# Esquema_V2.net
KiCad netlist of a schematic drawn in Altium Designer
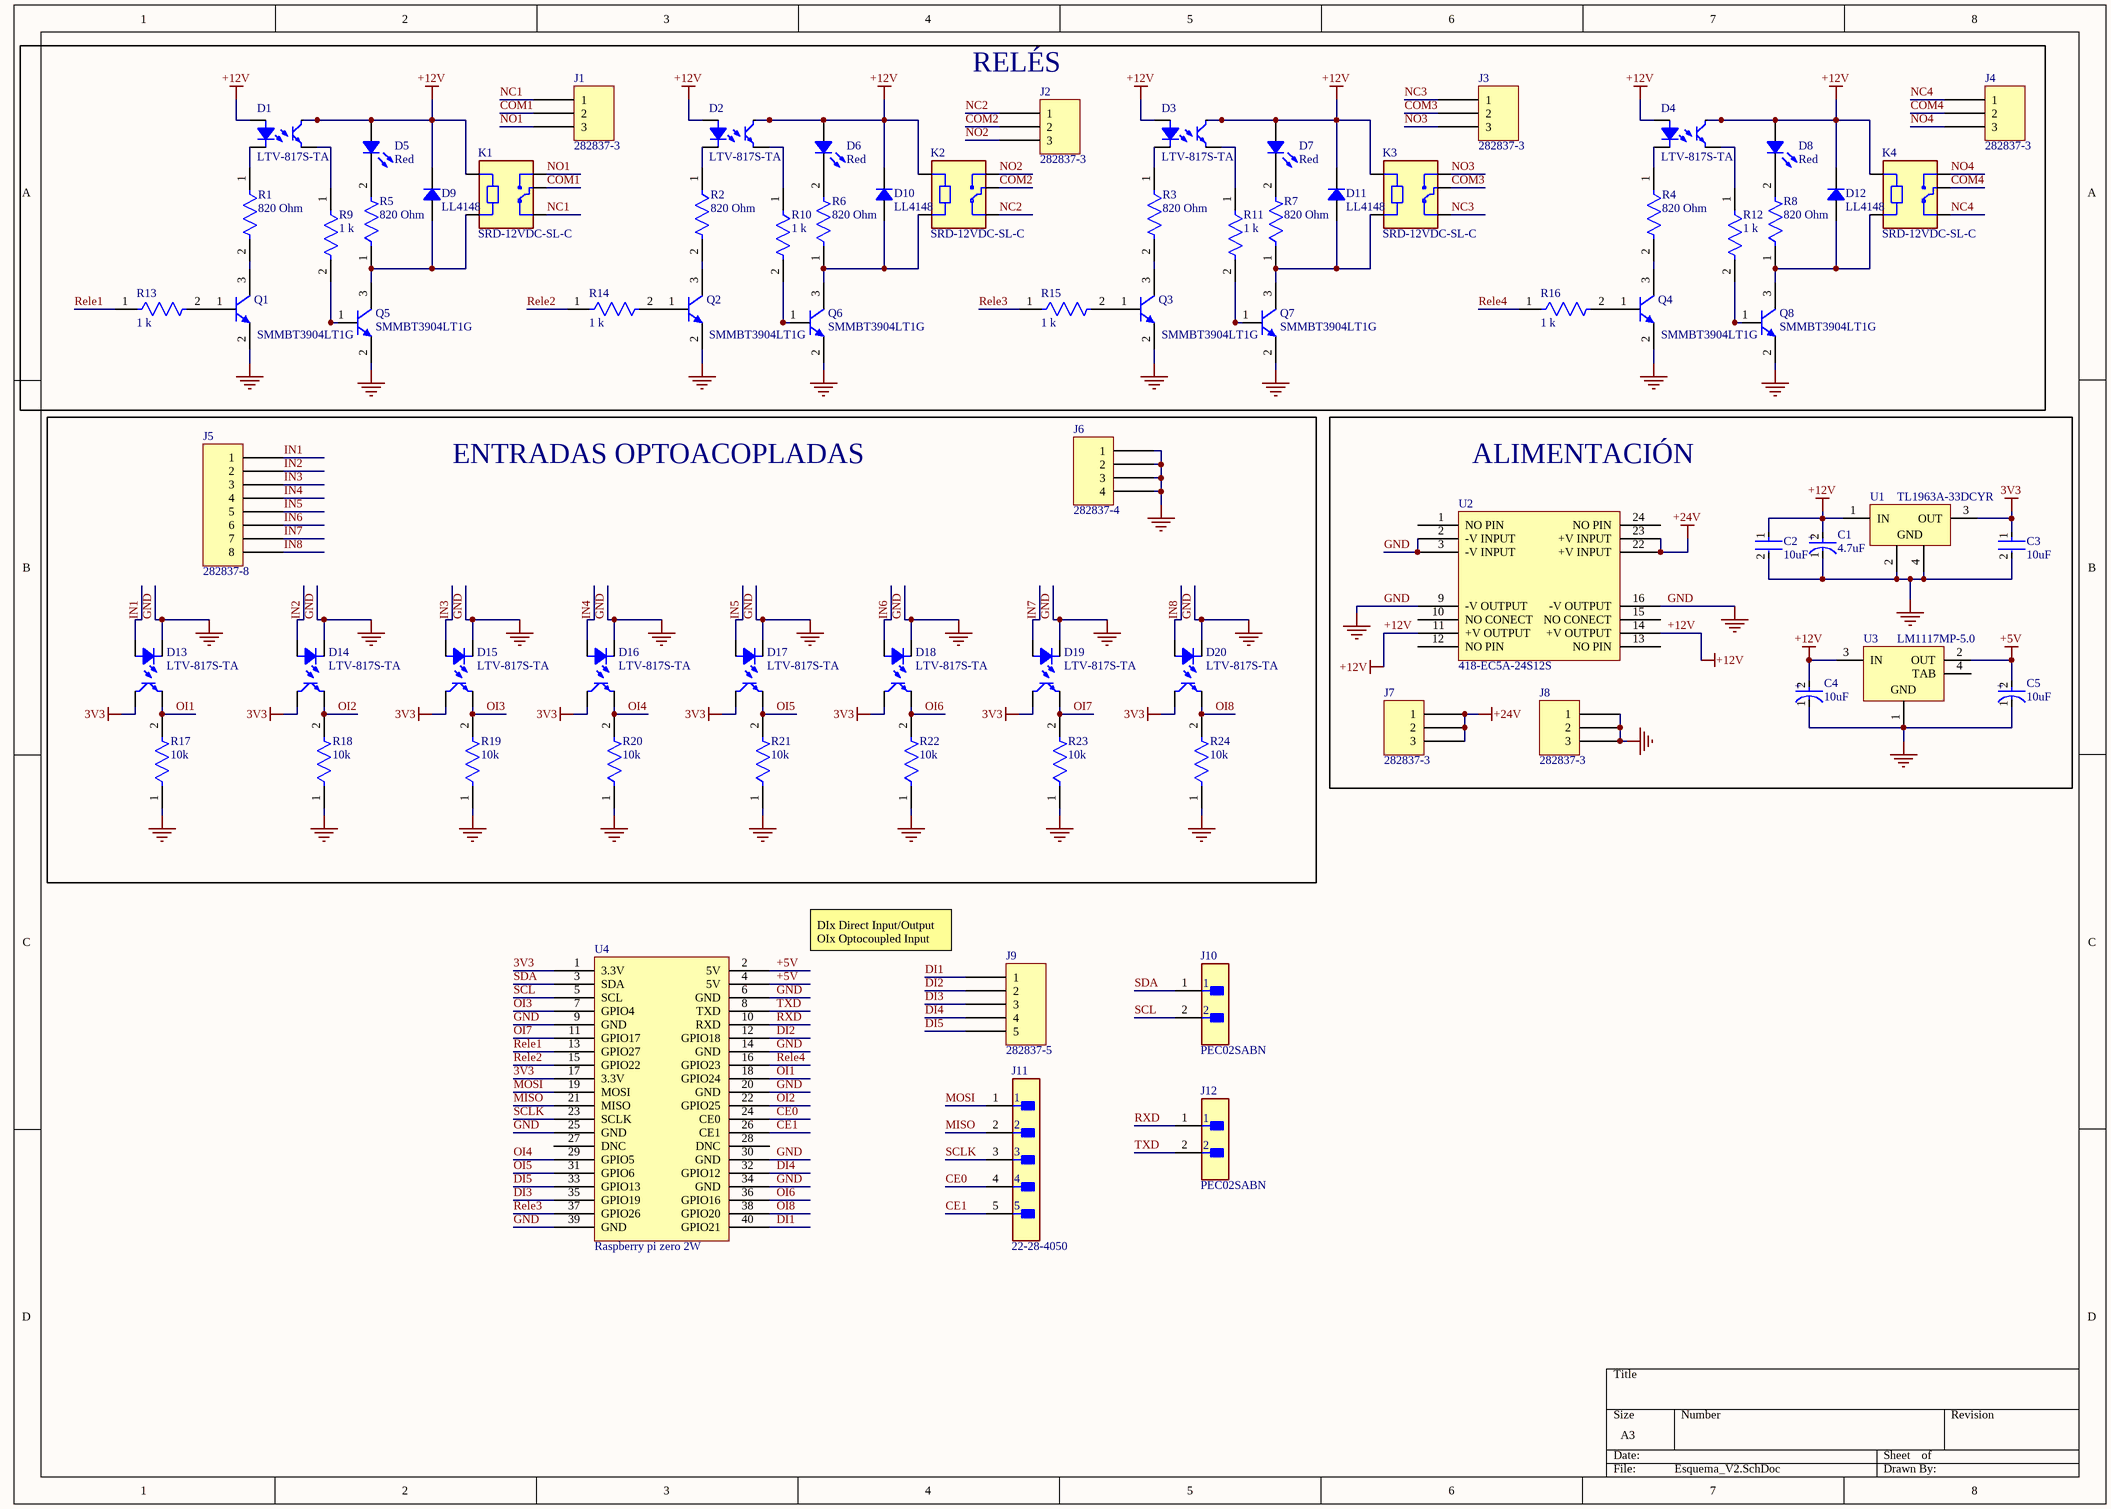
[diagram p0: Esquema_V2.SchDoc]

(export (version "E")
  (design (tool "Eeschema 10.0.6"))
  (components
    (comp (ref "C1")
      (value "4.7uF")
      (footprint "FP-T491A475M016AT-MFG")
      (description "T491A475M016AT CAP TANT 4.7UF 20% 16V 1206")
      (fields (field (name "TOLERANCE") "20%"))
      (libsource (lib "Altium Content Vault") (part "a00bbbee19879c290e62620ae7e47b1"))
    )
    (comp (ref "C2")
      (value "10uF")
      (footprint "FP-C2012-125-0_2-IPC_B")
      (description "C2012X5R1E106K125AB Multilayer Ceramic Capacitors 10μF ±10% 25V X5R SMD 0805")
      (fields (field (name "VOLTAGE") "25V") (field (name "TOLERANCE") "10%"))
      (libsource (lib "Altium Content Vault") (part "b4654b650e69147ec39a6b967a45e02"))
    )
    (comp (ref "C3")
      (value "10uF")
      (footprint "FP-C2012-125-0_2-IPC_B")
      (description "C2012X5R1E106K125AB Multilayer Ceramic Capacitors 10μF ±10% 25V X5R SMD 0805")
      (fields (field (name "VOLTAGE") "25V") (field (name "TOLERANCE") "10%"))
      (libsource (lib "Altium Content Vault") (part "b4654b650e69147ec39a6b967a45e02"))
    )
    (comp (ref "C4")
      (value "10uF")
      (footprint "FP-TAJA-MFG")
      (description "TAJA106M010RNJ 10uF 10V  ±20% 3Ω 1206  SMD Tantalum Capacitor")
      (fields (field (name "TOLERANCE") "20%") (field (name "VOLTAGE") "10V"))
      (libsource (lib "Altium Content Vault") (part "203bc49f2ac43e59fd269a8c329ed05"))
    )
    (comp (ref "C5")
      (value "10uF")
      (footprint "FP-TAJA-MFG")
      (description "TAJA106M010RNJ 10uF 10V  ±20% 3Ω 1206  SMD Tantalum Capacitor")
      (fields (field (name "TOLERANCE") "20%") (field (name "VOLTAGE") "10V"))
      (libsource (lib "Altium Content Vault") (part "203bc49f2ac43e59fd269a8c329ed05"))
    )
    (comp (ref "D1")
      (value "LTV-817S-TA")
      (footprint "LITEON LTV-817")
      (description "OPTOISOLATR 5KV TRANSISTOR 4-SMD")
      (fields (field (name "MANUFACTURER") "Lite-On Inc."))
      (libsource (lib "Celestial Altium Library - altium_library") (part "Optoisolator"))
    )
    (comp (ref "D2")
      (value "LTV-817S-TA")
      (footprint "LITEON LTV-817")
      (description "OPTOISOLATR 5KV TRANSISTOR 4-SMD")
      (fields (field (name "MANUFACTURER") "Lite-On Inc."))
      (libsource (lib "Celestial Altium Library - altium_library") (part "Optoisolator"))
    )
    (comp (ref "D3")
      (value "LTV-817S-TA")
      (footprint "LITEON LTV-817")
      (description "OPTOISOLATR 5KV TRANSISTOR 4-SMD")
      (fields (field (name "MANUFACTURER") "Lite-On Inc."))
      (libsource (lib "Celestial Altium Library - altium_library") (part "Optoisolator"))
    )
    (comp (ref "D4")
      (value "LTV-817S-TA")
      (footprint "LITEON LTV-817")
      (description "OPTOISOLATR 5KV TRANSISTOR 4-SMD")
      (fields (field (name "MANUFACTURER") "Lite-On Inc."))
      (libsource (lib "Celestial Altium Library - altium_library") (part "Optoisolator"))
    )
    (comp (ref "D5")
      (value "Red")
      (footprint "LED 1206_3216 RED")
      (description "LED RED CLEAR SMD")
      (fields (field (name "PART NUMBER") "LTST-C150KAKT") (field (name "MANUFACTURER") "Lite-On Inc."))
      (libsource (lib "Celestial Altium Library - altium_library") (part "LED"))
    )
    (comp (ref "D6")
      (value "Red")
      (footprint "LED 1206_3216 RED")
      (description "LED RED CLEAR SMD")
      (fields (field (name "PART NUMBER") "LTST-C150KAKT") (field (name "MANUFACTURER") "Lite-On Inc."))
      (libsource (lib "Celestial Altium Library - altium_library") (part "LED"))
    )
    (comp (ref "D7")
      (value "Red")
      (footprint "LED 1206_3216 RED")
      (description "LED RED CLEAR SMD")
      (fields (field (name "PART NUMBER") "LTST-C150KAKT") (field (name "MANUFACTURER") "Lite-On Inc."))
      (libsource (lib "Celestial Altium Library - altium_library") (part "LED"))
    )
    (comp (ref "D8")
      (value "Red")
      (footprint "LED 1206_3216 RED")
      (description "LED RED CLEAR SMD")
      (fields (field (name "PART NUMBER") "LTST-C150KAKT") (field (name "MANUFACTURER") "Lite-On Inc."))
      (libsource (lib "Celestial Altium Library - altium_library") (part "LED"))
    )
    (comp (ref "D9")
      (value "LL4148")
      (footprint "SOD-80 MiniMELF")
      (description "DIODE GEN PURP 100V 200MA SOD80")
      (fields (field (name "MANUFACTURER") "ON Semiconductor"))
      (libsource (lib "Celestial Altium Library - altium_library") (part "Diode"))
    )
    (comp (ref "D10")
      (value "LL4148")
      (footprint "SOD-80 MiniMELF")
      (description "DIODE GEN PURP 100V 200MA SOD80")
      (fields (field (name "MANUFACTURER") "ON Semiconductor"))
      (libsource (lib "Celestial Altium Library - altium_library") (part "Diode"))
    )
    (comp (ref "D11")
      (value "LL4148")
      (footprint "SOD-80 MiniMELF")
      (description "DIODE GEN PURP 100V 200MA SOD80")
      (fields (field (name "MANUFACTURER") "ON Semiconductor"))
      (libsource (lib "Celestial Altium Library - altium_library") (part "Diode"))
    )
    (comp (ref "D12")
      (value "LL4148")
      (footprint "SOD-80 MiniMELF")
      (description "DIODE GEN PURP 100V 200MA SOD80")
      (fields (field (name "MANUFACTURER") "ON Semiconductor"))
      (libsource (lib "Celestial Altium Library - altium_library") (part "Diode"))
    )
    (comp (ref "D13")
      (value "LTV-817S-TA")
      (footprint "LITEON LTV-817")
      (description "OPTOISOLATR 5KV TRANSISTOR 4-SMD")
      (fields (field (name "MANUFACTURER") "Lite-On Inc."))
      (libsource (lib "Celestial Altium Library - altium_library") (part "Optoisolator"))
    )
    (comp (ref "D14")
      (value "LTV-817S-TA")
      (footprint "LITEON LTV-817")
      (description "OPTOISOLATR 5KV TRANSISTOR 4-SMD")
      (fields (field (name "MANUFACTURER") "Lite-On Inc."))
      (libsource (lib "Celestial Altium Library - altium_library") (part "Optoisolator"))
    )
    (comp (ref "D15")
      (value "LTV-817S-TA")
      (footprint "LITEON LTV-817")
      (description "OPTOISOLATR 5KV TRANSISTOR 4-SMD")
      (fields (field (name "MANUFACTURER") "Lite-On Inc."))
      (libsource (lib "Celestial Altium Library - altium_library") (part "Optoisolator"))
    )
    (comp (ref "D16")
      (value "LTV-817S-TA")
      (footprint "LITEON LTV-817")
      (description "OPTOISOLATR 5KV TRANSISTOR 4-SMD")
      (fields (field (name "MANUFACTURER") "Lite-On Inc."))
      (libsource (lib "Celestial Altium Library - altium_library") (part "Optoisolator"))
    )
    (comp (ref "D17")
      (value "LTV-817S-TA")
      (footprint "LITEON LTV-817")
      (description "OPTOISOLATR 5KV TRANSISTOR 4-SMD")
      (fields (field (name "MANUFACTURER") "Lite-On Inc."))
      (libsource (lib "Celestial Altium Library - altium_library") (part "Optoisolator"))
    )
    (comp (ref "D18")
      (value "LTV-817S-TA")
      (footprint "LITEON LTV-817")
      (description "OPTOISOLATR 5KV TRANSISTOR 4-SMD")
      (fields (field (name "MANUFACTURER") "Lite-On Inc."))
      (libsource (lib "Celestial Altium Library - altium_library") (part "Optoisolator"))
    )
    (comp (ref "D19")
      (value "LTV-817S-TA")
      (footprint "LITEON LTV-817")
      (description "OPTOISOLATR 5KV TRANSISTOR 4-SMD")
      (fields (field (name "MANUFACTURER") "Lite-On Inc."))
      (libsource (lib "Celestial Altium Library - altium_library") (part "Optoisolator"))
    )
    (comp (ref "D20")
      (value "LTV-817S-TA")
      (footprint "LITEON LTV-817")
      (description "OPTOISOLATR 5KV TRANSISTOR 4-SMD")
      (fields (field (name "MANUFACTURER") "Lite-On Inc."))
      (libsource (lib "Celestial Altium Library - altium_library") (part "Optoisolator"))
    )
    (comp (ref "J1")
      (value "282837-3")
      (footprint "TE 282837-3")
      (description "TERM BLK 3P SIDE ENT 5.08MM PCB")
      (fields (field (name "MANUFACTURER") "TE Connectivity AMP Connectors") (field (name "VOLTAGE") "300 V"))
      (libsource (lib "") (part "3 Pin_1"))
    )
    (comp (ref "J2")
      (value "282837-3")
      (footprint "TE 282837-3")
      (description "TERM BLK 3P SIDE ENT 5.08MM PCB")
      (fields (field (name "MANUFACTURER") "TE Connectivity AMP Connectors") (field (name "VOLTAGE") "300 V"))
      (libsource (lib "") (part "3 Pin_1"))
    )
    (comp (ref "J3")
      (value "282837-3")
      (footprint "TE 282837-3")
      (description "TERM BLK 3P SIDE ENT 5.08MM PCB")
      (fields (field (name "MANUFACTURER") "TE Connectivity AMP Connectors") (field (name "VOLTAGE") "300 V"))
      (libsource (lib "") (part "3 Pin_1"))
    )
    (comp (ref "J4")
      (value "282837-3")
      (footprint "TE 282837-3")
      (description "TERM BLK 3P SIDE ENT 5.08MM PCB")
      (fields (field (name "MANUFACTURER") "TE Connectivity AMP Connectors") (field (name "VOLTAGE") "300 V"))
      (libsource (lib "") (part "3 Pin_1"))
    )
    (comp (ref "J5")
      (value "282837-8")
      (footprint "TE 282837-8")
      (description "TERM BLK 8P SIDE ENT 5.08MM PCB")
      (fields (field (name "MANUFACTURER") "TE Connectivity AMP Connectors") (field (name "VOLTAGE") "300 V"))
      (libsource (lib "Celestial Altium Library - altium_library") (part "8 Pin"))
    )
    (comp (ref "J6")
      (value "282837-4")
      (footprint "TE 282837-4")
      (description "TERM BLK 4P SIDE ENT 5.08MM PCB")
      (fields (field (name "MANUFACTURER") "TE Connectivity AMP Connectors") (field (name "VOLTAGE") "300 V"))
      (libsource (lib "Celestial Altium Library - altium_library") (part "4 Pin"))
    )
    (comp (ref "J7")
      (value "282837-3")
      (footprint "TE 282837-3")
      (description "TERM BLK 3P SIDE ENT 5.08MM PCB")
      (fields (field (name "MANUFACTURER") "TE Connectivity AMP Connectors") (field (name "VOLTAGE") "300 V"))
      (libsource (lib "Celestial Altium Library - altium_library") (part "3 Pin"))
    )
    (comp (ref "J8")
      (value "282837-3")
      (footprint "TE 282837-3")
      (description "TERM BLK 3P SIDE ENT 5.08MM PCB")
      (fields (field (name "MANUFACTURER") "TE Connectivity AMP Connectors") (field (name "VOLTAGE") "300 V"))
      (libsource (lib "Celestial Altium Library - altium_library") (part "3 Pin"))
    )
    (comp (ref "J9")
      (value "282837-5")
      (footprint "TE 282837-5")
      (description "TERM BLK 5P SIDE ENT 5.08MM PCB")
      (fields (field (name "MANUFACTURER") "TE Connectivity AMP Connectors") (field (name "VOLTAGE") "300V"))
      (libsource (lib "Celestial Altium Library - altium_library") (part "5 Pin"))
    )
    (comp (ref "J10")
      (value "PEC02SABN")
      (footprint "FP-PEC02SABN-MFG")
      (description "CONN HEADER VERT 2POS 2.54MM")
      (libsource (lib "Altium Content Vault") (part "3bc925449376181038e59eaffc5286c"))
    )
    (comp (ref "J11")
      (value "22-28-4050")
      (footprint "FP-22-28-4050-MFG")
      (libsource (lib "Altium Content Vault") (part "bf93c07fd2649a848d0ec8585582aab"))
    )
    (comp (ref "J12")
      (value "PEC02SABN")
      (footprint "FP-PEC02SABN-MFG")
      (description "CONN HEADER VERT 2POS 2.54MM")
      (libsource (lib "Altium Content Vault") (part "3bc925449376181038e59eaffc5286c"))
    )
    (comp (ref "K1")
      (value "SRD-12VDC-SL-C")
      (footprint "RELAY_SRD-05VDC-SL-C")
      (fields (field (name "MF") "Songle Relay") (field (name "MP") "SRD-05VDC-SL-C"))
      (libsource (lib "SRD-05VDC-SL-C") (part "SRD-05VDC-SL-C"))
    )
    (comp (ref "K2")
      (value "SRD-12VDC-SL-C")
      (footprint "RELAY_SRD-05VDC-SL-C")
      (fields (field (name "MF") "Songle Relay") (field (name "MP") "SRD-05VDC-SL-C"))
      (libsource (lib "SRD-05VDC-SL-C") (part "SRD-05VDC-SL-C"))
    )
    (comp (ref "K3")
      (value "SRD-12VDC-SL-C")
      (footprint "RELAY_SRD-05VDC-SL-C")
      (fields (field (name "MF") "Songle Relay") (field (name "MP") "SRD-05VDC-SL-C"))
      (libsource (lib "SRD-05VDC-SL-C") (part "SRD-05VDC-SL-C"))
    )
    (comp (ref "K4")
      (value "SRD-12VDC-SL-C")
      (footprint "RELAY_SRD-05VDC-SL-C")
      (fields (field (name "MF") "Songle Relay") (field (name "MP") "SRD-05VDC-SL-C"))
      (libsource (lib "SRD-05VDC-SL-C") (part "SRD-05VDC-SL-C"))
    )
    (comp (ref "Q1")
      (value "SMMBT3904LT1G")
      (footprint "ONSC-SOT-23-3-318-08_V")
      (description "General Purpose Transistor, NPN Silicon, 3-Pin SOT-23, Pb-Free, Tape and Reel")
      (fields (field (name "MANUFACTURER") "On Semiconductor"))
      (libsource (lib "Altium Content Vault") (part "ONSC-NPN-B1E2C3-3"))
    )
    (comp (ref "Q2")
      (value "SMMBT3904LT1G")
      (footprint "ONSC-SOT-23-3-318-08_V")
      (description "General Purpose Transistor, NPN Silicon, 3-Pin SOT-23, Pb-Free, Tape and Reel")
      (fields (field (name "MANUFACTURER") "On Semiconductor"))
      (libsource (lib "Altium Content Vault") (part "ONSC-NPN-B1E2C3-3"))
    )
    (comp (ref "Q3")
      (value "SMMBT3904LT1G")
      (footprint "ONSC-SOT-23-3-318-08_V")
      (description "General Purpose Transistor, NPN Silicon, 3-Pin SOT-23, Pb-Free, Tape and Reel")
      (fields (field (name "MANUFACTURER") "On Semiconductor"))
      (libsource (lib "Altium Content Vault") (part "ONSC-NPN-B1E2C3-3"))
    )
    (comp (ref "Q4")
      (value "SMMBT3904LT1G")
      (footprint "ONSC-SOT-23-3-318-08_V")
      (description "General Purpose Transistor, NPN Silicon, 3-Pin SOT-23, Pb-Free, Tape and Reel")
      (fields (field (name "MANUFACTURER") "On Semiconductor"))
      (libsource (lib "Altium Content Vault") (part "ONSC-NPN-B1E2C3-3"))
    )
    (comp (ref "Q5")
      (value "SMMBT3904LT1G")
      (footprint "ONSC-SOT-23-3-318-08_V")
      (description "General Purpose Transistor, NPN Silicon, 3-Pin SOT-23, Pb-Free, Tape and Reel")
      (fields (field (name "MANUFACTURER") "On Semiconductor"))
      (libsource (lib "Altium Content Vault") (part "ONSC-NPN-B1E2C3-3"))
    )
    (comp (ref "Q6")
      (value "SMMBT3904LT1G")
      (footprint "ONSC-SOT-23-3-318-08_V")
      (description "General Purpose Transistor, NPN Silicon, 3-Pin SOT-23, Pb-Free, Tape and Reel")
      (fields (field (name "MANUFACTURER") "On Semiconductor"))
      (libsource (lib "Altium Content Vault") (part "ONSC-NPN-B1E2C3-3"))
    )
    (comp (ref "Q7")
      (value "SMMBT3904LT1G")
      (footprint "ONSC-SOT-23-3-318-08_V")
      (description "General Purpose Transistor, NPN Silicon, 3-Pin SOT-23, Pb-Free, Tape and Reel")
      (fields (field (name "MANUFACTURER") "On Semiconductor"))
      (libsource (lib "Altium Content Vault") (part "ONSC-NPN-B1E2C3-3"))
    )
    (comp (ref "Q8")
      (value "SMMBT3904LT1G")
      (footprint "ONSC-SOT-23-3-318-08_V")
      (description "General Purpose Transistor, NPN Silicon, 3-Pin SOT-23, Pb-Free, Tape and Reel")
      (fields (field (name "MANUFACTURER") "On Semiconductor"))
      (libsource (lib "Altium Content Vault") (part "ONSC-NPN-B1E2C3-3"))
    )
    (comp (ref "R1")
      (value "820 Ohm")
      (footprint "FP-CRCW0603-HPe3-MFG")
      (description "RES Thick Film, 820Ω, 1%, 0.33W, 100ppm/°C, 0603")
      (fields (field (name "TOLERANCE") "1%"))
      (libsource (lib "Altium Content Vault") (part "1029c3af85768c4190bb7ad29bc67b5"))
    )
    (comp (ref "R2")
      (value "820 Ohm")
      (footprint "FP-CRCW0603-HPe3-MFG")
      (description "RES Thick Film, 820Ω, 1%, 0.33W, 100ppm/°C, 0603")
      (fields (field (name "TOLERANCE") "1%"))
      (libsource (lib "Altium Content Vault") (part "1029c3af85768c4190bb7ad29bc67b5"))
    )
    (comp (ref "R3")
      (value "820 Ohm")
      (footprint "FP-CRCW0603-HPe3-MFG")
      (description "RES Thick Film, 820Ω, 1%, 0.33W, 100ppm/°C, 0603")
      (fields (field (name "TOLERANCE") "1%"))
      (libsource (lib "Altium Content Vault") (part "1029c3af85768c4190bb7ad29bc67b5"))
    )
    (comp (ref "R4")
      (value "820 Ohm")
      (footprint "FP-CRCW0603-HPe3-MFG")
      (description "RES Thick Film, 820Ω, 1%, 0.33W, 100ppm/°C, 0603")
      (fields (field (name "TOLERANCE") "1%"))
      (libsource (lib "Altium Content Vault") (part "1029c3af85768c4190bb7ad29bc67b5"))
    )
    (comp (ref "R5")
      (value "820 Ohm")
      (footprint "FP-CRCW0603-HPe3-MFG")
      (description "RES Thick Film, 820Ω, 1%, 0.33W, 100ppm/°C, 0603")
      (fields (field (name "TOLERANCE") "1%"))
      (libsource (lib "Altium Content Vault") (part "1029c3af85768c4190bb7ad29bc67b5"))
    )
    (comp (ref "R6")
      (value "820 Ohm")
      (footprint "FP-CRCW0603-HPe3-MFG")
      (description "RES Thick Film, 820Ω, 1%, 0.33W, 100ppm/°C, 0603")
      (fields (field (name "TOLERANCE") "1%"))
      (libsource (lib "Altium Content Vault") (part "1029c3af85768c4190bb7ad29bc67b5"))
    )
    (comp (ref "R7")
      (value "820 Ohm")
      (footprint "FP-CRCW0603-HPe3-MFG")
      (description "RES Thick Film, 820Ω, 1%, 0.33W, 100ppm/°C, 0603")
      (fields (field (name "TOLERANCE") "1%"))
      (libsource (lib "Altium Content Vault") (part "1029c3af85768c4190bb7ad29bc67b5"))
    )
    (comp (ref "R8")
      (value "820 Ohm")
      (footprint "FP-CRCW0603-HPe3-MFG")
      (description "RES Thick Film, 820Ω, 1%, 0.33W, 100ppm/°C, 0603")
      (fields (field (name "TOLERANCE") "1%"))
      (libsource (lib "Altium Content Vault") (part "1029c3af85768c4190bb7ad29bc67b5"))
    )
    (comp (ref "R9")
      (value "1 k")
      (footprint "FP-MCT0603-IPC_C")
      (description "MCT0603PD1001DP500 RES SMD 100 OHM 1% 1/8W 0603")
      (fields (field (name "TOLERANCE") "0.5%"))
      (libsource (lib "Altium Content Vault") (part "1029c3af85768c4190bb7ad29bc67b5"))
    )
    (comp (ref "R10")
      (value "1 k")
      (footprint "FP-MCT0603-IPC_C")
      (description "MCT0603PD1001DP500 RES SMD 100 OHM 1% 1/8W 0603")
      (fields (field (name "TOLERANCE") "0.5%"))
      (libsource (lib "Altium Content Vault") (part "1029c3af85768c4190bb7ad29bc67b5"))
    )
    (comp (ref "R11")
      (value "1 k")
      (footprint "FP-MCT0603-IPC_C")
      (description "MCT0603PD1001DP500 RES SMD 100 OHM 1% 1/8W 0603")
      (fields (field (name "TOLERANCE") "0.5%"))
      (libsource (lib "Altium Content Vault") (part "1029c3af85768c4190bb7ad29bc67b5"))
    )
    (comp (ref "R12")
      (value "1 k")
      (footprint "FP-MCT0603-IPC_C")
      (description "MCT0603PD1001DP500 RES SMD 100 OHM 1% 1/8W 0603")
      (fields (field (name "TOLERANCE") "0.5%"))
      (libsource (lib "Altium Content Vault") (part "1029c3af85768c4190bb7ad29bc67b5"))
    )
    (comp (ref "R13")
      (value "1 k")
      (footprint "FP-MCT0603-IPC_C")
      (description "MCT0603PD1001DP500 RES SMD 100 OHM 1% 1/8W 0603")
      (fields (field (name "TOLERANCE") "0.5%"))
      (libsource (lib "Altium Content Vault") (part "1029c3af85768c4190bb7ad29bc67b5"))
    )
    (comp (ref "R14")
      (value "1 k")
      (footprint "FP-MCT0603-IPC_C")
      (description "MCT0603PD1001DP500 RES SMD 100 OHM 1% 1/8W 0603")
      (fields (field (name "TOLERANCE") "0.5%"))
      (libsource (lib "Altium Content Vault") (part "1029c3af85768c4190bb7ad29bc67b5"))
    )
    (comp (ref "R15")
      (value "1 k")
      (footprint "FP-MCT0603-IPC_C")
      (description "MCT0603PD1001DP500 RES SMD 100 OHM 1% 1/8W 0603")
      (fields (field (name "TOLERANCE") "0.5%"))
      (libsource (lib "Altium Content Vault") (part "1029c3af85768c4190bb7ad29bc67b5"))
    )
    (comp (ref "R16")
      (value "1 k")
      (footprint "FP-MCT0603-IPC_C")
      (description "MCT0603PD1001DP500 RES SMD 100 OHM 1% 1/8W 0603")
      (fields (field (name "TOLERANCE") "0.5%"))
      (libsource (lib "Altium Content Vault") (part "1029c3af85768c4190bb7ad29bc67b5"))
    )
    (comp (ref "R17")
      (value "10k")
      (footprint "FP-MCT0603-IPC_B")
      (description "MCT0603MD1002BP100 RES SMD 10k OHM 1% 1/8W 0603")
      (fields (field (name "TOLERANCE") "0.1%"))
      (libsource (lib "Altium Content Vault") (part "1029c3af85768c4190bb7ad29bc67b5"))
    )
    (comp (ref "R18")
      (value "10k")
      (footprint "FP-MCT0603-IPC_B")
      (description "MCT0603MD1002BP100 RES SMD 10k OHM 1% 1/8W 0603")
      (fields (field (name "TOLERANCE") "0.1%"))
      (libsource (lib "Altium Content Vault") (part "1029c3af85768c4190bb7ad29bc67b5"))
    )
    (comp (ref "R19")
      (value "10k")
      (footprint "FP-MCT0603-IPC_B")
      (description "MCT0603MD1002BP100 RES SMD 10k OHM 1% 1/8W 0603")
      (fields (field (name "TOLERANCE") "0.1%"))
      (libsource (lib "Altium Content Vault") (part "1029c3af85768c4190bb7ad29bc67b5"))
    )
    (comp (ref "R20")
      (value "10k")
      (footprint "FP-MCT0603-IPC_B")
      (description "MCT0603MD1002BP100 RES SMD 10k OHM 1% 1/8W 0603")
      (fields (field (name "TOLERANCE") "0.1%"))
      (libsource (lib "Altium Content Vault") (part "1029c3af85768c4190bb7ad29bc67b5"))
    )
    (comp (ref "R21")
      (value "10k")
      (footprint "FP-MCT0603-IPC_B")
      (description "MCT0603MD1002BP100 RES SMD 10k OHM 1% 1/8W 0603")
      (fields (field (name "TOLERANCE") "0.1%"))
      (libsource (lib "Altium Content Vault") (part "1029c3af85768c4190bb7ad29bc67b5"))
    )
    (comp (ref "R22")
      (value "10k")
      (footprint "FP-MCT0603-IPC_B")
      (description "MCT0603MD1002BP100 RES SMD 10k OHM 1% 1/8W 0603")
      (fields (field (name "TOLERANCE") "0.1%"))
      (libsource (lib "Altium Content Vault") (part "1029c3af85768c4190bb7ad29bc67b5"))
    )
    (comp (ref "R23")
      (value "10k")
      (footprint "FP-MCT0603-IPC_B")
      (description "MCT0603MD1002BP100 RES SMD 10k OHM 1% 1/8W 0603")
      (fields (field (name "TOLERANCE") "0.1%"))
      (libsource (lib "Altium Content Vault") (part "1029c3af85768c4190bb7ad29bc67b5"))
    )
    (comp (ref "R24")
      (value "10k")
      (footprint "FP-MCT0603-IPC_B")
      (description "MCT0603MD1002BP100 RES SMD 10k OHM 1% 1/8W 0603")
      (fields (field (name "TOLERANCE") "0.1%"))
      (libsource (lib "Altium Content Vault") (part "1029c3af85768c4190bb7ad29bc67b5"))
    )
    (comp (ref "U1")
      (value "TL1963A-33DCYR")
      (footprint "DCY0004A_N")
      (fields (field (name "MANUFACTURER") "Texas Instruments"))
      (libsource (lib "Altium Content Vault") (part "TI-TL1963A-XXDCY4"))
    )
    (comp (ref "U2")
      (value "418-EC5A-24S12S")
      (footprint "418-EC5A-24S12S")
      (libsource (lib "Raspberry") (part "418-EC5A-24S12S"))
    )
    (comp (ref "U3")
      (value "LM1117MP-5.0")
      (footprint "MP04A_N")
      (description "800mA Low-Dropout Linear Regulator, 4-pin SOT-223")
      (fields (field (name "MANUFACTURER") "National Semiconductor"))
      (libsource (lib "Altium Content Vault") (part "PM-REG-LM1086-SOT4"))
    )
    (comp (ref "U4")
      (value "Raspberry pi zero 2W")
      (footprint "PCBComponent_1")
      (libsource (lib "Raspberry") (part "Raspberry pi zero 2W"))
    )
  )
  (nets
    (net (code "1") (name "+5V") (class "Default")
      (node (ref "C5") (pin "2") (pinfunction "A_2") (pintype "passive"))
      (node (ref "U3") (pin "2") (pinfunction "OUT_2") (pintype "power_in"))
      (node (ref "U4") (pin "2") (pinfunction "5V_2") (pintype "passive"))
      (node (ref "U4") (pin "4") (pinfunction "5V_4") (pintype "passive"))
    )
    (net (code "2") (name "+12V") (class "Default")
      (node (ref "C1") (pin "2") (pinfunction "A_2") (pintype "passive"))
      (node (ref "C2") (pin "1") (pinfunction "1_1") (pintype "passive"))
      (node (ref "C4") (pin "2") (pinfunction "A_2") (pintype "passive"))
      (node (ref "D1") (pin "1") (pinfunction "1_1") (pintype "passive"))
      (node (ref "D1") (pin "4") (pinfunction "4_4") (pintype "passive"))
      (node (ref "D10") (pin "2") (pinfunction "2_2") (pintype "passive"))
      (node (ref "D11") (pin "2") (pinfunction "2_2") (pintype "passive"))
      (node (ref "D12") (pin "2") (pinfunction "2_2") (pintype "passive"))
      (node (ref "D2") (pin "1") (pinfunction "1_1") (pintype "passive"))
      (node (ref "D2") (pin "4") (pinfunction "4_4") (pintype "passive"))
      (node (ref "D3") (pin "1") (pinfunction "1_1") (pintype "passive"))
      (node (ref "D3") (pin "4") (pinfunction "4_4") (pintype "passive"))
      (node (ref "D4") (pin "1") (pinfunction "1_1") (pintype "passive"))
      (node (ref "D4") (pin "4") (pinfunction "4_4") (pintype "passive"))
      (node (ref "D5") (pin "1") (pinfunction "1_1") (pintype "passive"))
      (node (ref "D6") (pin "1") (pinfunction "1_1") (pintype "passive"))
      (node (ref "D7") (pin "1") (pinfunction "1_1") (pintype "passive"))
      (node (ref "D8") (pin "1") (pinfunction "1_1") (pintype "passive"))
      (node (ref "D9") (pin "2") (pinfunction "2_2") (pintype "passive"))
      (node (ref "K1") (pin "A1") (pinfunction "A1_A1") (pintype "passive"))
      (node (ref "K2") (pin "A1") (pinfunction "A1_A1") (pintype "passive"))
      (node (ref "K3") (pin "A1") (pinfunction "A1_A1") (pintype "passive"))
      (node (ref "K4") (pin "A1") (pinfunction "A1_A1") (pintype "passive"))
      (node (ref "U1") (pin "1") (pinfunction "IN_1") (pintype "power_in"))
      (node (ref "U2") (pin "11") (pinfunction "+V_OUTPUT_11") (pintype "passive"))
      (node (ref "U2") (pin "14") (pinfunction "+V_OUTPUT_14") (pintype "passive"))
      (node (ref "U3") (pin "3") (pinfunction "IN_3") (pintype "power_in"))
    )
    (net (code "3") (name "+24V") (class "Default")
      (node (ref "J7") (pin "1") (pinfunction "1_1") (pintype "passive"))
      (node (ref "J7") (pin "2") (pinfunction "2_2") (pintype "passive"))
      (node (ref "J7") (pin "3") (pinfunction "3_3") (pintype "passive"))
      (node (ref "U2") (pin "22") (pinfunction "+V_INPUT_22") (pintype "passive"))
      (node (ref "U2") (pin "23") (pinfunction "+V_INPUT_23") (pintype "passive"))
    )
    (net (code "4") (name "/CE0") (class "Default")
      (node (ref "J11") (pin "4") (pinfunction "4_4") (pintype "passive"))
      (node (ref "U4") (pin "24") (pinfunction "CE0_24") (pintype "passive"))
    )
    (net (code "5") (name "/CE1") (class "Default")
      (node (ref "J11") (pin "5") (pinfunction "5_5") (pintype "passive"))
      (node (ref "U4") (pin "26") (pinfunction "CE1_26") (pintype "passive"))
    )
    (net (code "6") (name "/COM1") (class "Default")
      (node (ref "J1") (pin "2") (pinfunction "2_2") (pintype "passive"))
      (node (ref "K1") (pin "COM") (pinfunction "COM_COM") (pintype "passive"))
    )
    (net (code "7") (name "/COM2") (class "Default")
      (node (ref "J2") (pin "2") (pinfunction "2_2") (pintype "passive"))
      (node (ref "K2") (pin "COM") (pinfunction "COM_COM") (pintype "passive"))
    )
    (net (code "8") (name "/COM3") (class "Default")
      (node (ref "J3") (pin "2") (pinfunction "2_2") (pintype "passive"))
      (node (ref "K3") (pin "COM") (pinfunction "COM_COM") (pintype "passive"))
    )
    (net (code "9") (name "/COM4") (class "Default")
      (node (ref "J4") (pin "2") (pinfunction "2_2") (pintype "passive"))
      (node (ref "K4") (pin "COM") (pinfunction "COM_COM") (pintype "passive"))
    )
    (net (code "10") (name "/DI1") (class "Default")
      (node (ref "J9") (pin "1") (pinfunction "1_1") (pintype "passive"))
      (node (ref "U4") (pin "40") (pinfunction "GPIO21_40") (pintype "passive"))
    )
    (net (code "11") (name "/DI2") (class "Default")
      (node (ref "J9") (pin "2") (pinfunction "2_2") (pintype "passive"))
      (node (ref "U4") (pin "12") (pinfunction "GPIO18_12") (pintype "passive"))
    )
    (net (code "12") (name "/DI3") (class "Default")
      (node (ref "J9") (pin "3") (pinfunction "3_3") (pintype "passive"))
      (node (ref "U4") (pin "35") (pinfunction "GPIO19_35") (pintype "passive"))
    )
    (net (code "13") (name "/DI4") (class "Default")
      (node (ref "J9") (pin "4") (pinfunction "4_4") (pintype "passive"))
      (node (ref "U4") (pin "32") (pinfunction "GPIO12_32") (pintype "passive"))
    )
    (net (code "14") (name "/DI5") (class "Default")
      (node (ref "J9") (pin "5") (pinfunction "5_5") (pintype "passive"))
      (node (ref "U4") (pin "33") (pinfunction "GPIO13_33") (pintype "passive"))
    )
    (net (code "15") (name "/IN1") (class "Default")
      (node (ref "D13") (pin "1") (pinfunction "1_1") (pintype "passive"))
      (node (ref "J5") (pin "1") (pinfunction "1_1") (pintype "passive"))
    )
    (net (code "16") (name "/IN2") (class "Default")
      (node (ref "D14") (pin "1") (pinfunction "1_1") (pintype "passive"))
      (node (ref "J5") (pin "2") (pinfunction "2_2") (pintype "passive"))
    )
    (net (code "17") (name "/IN3") (class "Default")
      (node (ref "D15") (pin "1") (pinfunction "1_1") (pintype "passive"))
      (node (ref "J5") (pin "3") (pinfunction "3_3") (pintype "passive"))
    )
    (net (code "18") (name "/IN4") (class "Default")
      (node (ref "D16") (pin "1") (pinfunction "1_1") (pintype "passive"))
      (node (ref "J5") (pin "4") (pinfunction "4_4") (pintype "passive"))
    )
    (net (code "19") (name "/IN5") (class "Default")
      (node (ref "D17") (pin "1") (pinfunction "1_1") (pintype "passive"))
      (node (ref "J5") (pin "5") (pinfunction "5_5") (pintype "passive"))
    )
    (net (code "20") (name "/IN6") (class "Default")
      (node (ref "D18") (pin "1") (pinfunction "1_1") (pintype "passive"))
      (node (ref "J5") (pin "6") (pinfunction "6_6") (pintype "passive"))
    )
    (net (code "21") (name "/IN7") (class "Default")
      (node (ref "D19") (pin "1") (pinfunction "1_1") (pintype "passive"))
      (node (ref "J5") (pin "7") (pinfunction "7_7") (pintype "passive"))
    )
    (net (code "22") (name "/IN8") (class "Default")
      (node (ref "D20") (pin "1") (pinfunction "1_1") (pintype "passive"))
      (node (ref "J5") (pin "8") (pinfunction "8_8") (pintype "passive"))
    )
    (net (code "23") (name "/MISO") (class "Default")
      (node (ref "J11") (pin "2") (pinfunction "2_2") (pintype "passive"))
      (node (ref "U4") (pin "21") (pinfunction "MISO_21") (pintype "passive"))
    )
    (net (code "24") (name "/MOSI") (class "Default")
      (node (ref "J11") (pin "1") (pinfunction "1_1") (pintype "passive"))
      (node (ref "U4") (pin "19") (pinfunction "MOSI_19") (pintype "passive"))
    )
    (net (code "25") (name "/NC1") (class "Default")
      (node (ref "J1") (pin "1") (pinfunction "1_1") (pintype "passive"))
      (node (ref "K1") (pin "NC") (pinfunction "NC_NC") (pintype "passive"))
    )
    (net (code "26") (name "/NC2") (class "Default")
      (node (ref "J2") (pin "1") (pinfunction "1_1") (pintype "passive"))
      (node (ref "K2") (pin "NC") (pinfunction "NC_NC") (pintype "passive"))
    )
    (net (code "27") (name "/NC3") (class "Default")
      (node (ref "J3") (pin "1") (pinfunction "1_1") (pintype "passive"))
      (node (ref "K3") (pin "NC") (pinfunction "NC_NC") (pintype "passive"))
    )
    (net (code "28") (name "/NC4") (class "Default")
      (node (ref "J4") (pin "1") (pinfunction "1_1") (pintype "passive"))
      (node (ref "K4") (pin "NC") (pinfunction "NC_NC") (pintype "passive"))
    )
    (net (code "29") (name "/NO1") (class "Default")
      (node (ref "J1") (pin "3") (pinfunction "3_3") (pintype "passive"))
      (node (ref "K1") (pin "NO") (pinfunction "NO_NO") (pintype "passive"))
    )
    (net (code "30") (name "/NO2") (class "Default")
      (node (ref "J2") (pin "3") (pinfunction "3_3") (pintype "passive"))
      (node (ref "K2") (pin "NO") (pinfunction "NO_NO") (pintype "passive"))
    )
    (net (code "31") (name "/NO3") (class "Default")
      (node (ref "J3") (pin "3") (pinfunction "3_3") (pintype "passive"))
      (node (ref "K3") (pin "NO") (pinfunction "NO_NO") (pintype "passive"))
    )
    (net (code "32") (name "/NO4") (class "Default")
      (node (ref "J4") (pin "3") (pinfunction "3_3") (pintype "passive"))
      (node (ref "K4") (pin "NO") (pinfunction "NO_NO") (pintype "passive"))
    )
    (net (code "33") (name "/OI1") (class "Default")
      (node (ref "D13") (pin "3") (pinfunction "3_3") (pintype "passive"))
      (node (ref "R17") (pin "2") (pinfunction "2_2") (pintype "passive"))
      (node (ref "U4") (pin "18") (pinfunction "GPIO24_18") (pintype "passive"))
    )
    (net (code "34") (name "/OI2") (class "Default")
      (node (ref "D14") (pin "3") (pinfunction "3_3") (pintype "passive"))
      (node (ref "R18") (pin "2") (pinfunction "2_2") (pintype "passive"))
      (node (ref "U4") (pin "22") (pinfunction "GPIO25_22") (pintype "passive"))
    )
    (net (code "35") (name "/OI3") (class "Default")
      (node (ref "D15") (pin "3") (pinfunction "3_3") (pintype "passive"))
      (node (ref "R19") (pin "2") (pinfunction "2_2") (pintype "passive"))
      (node (ref "U4") (pin "7") (pinfunction "GPIO4_7") (pintype "passive"))
    )
    (net (code "36") (name "/OI4") (class "Default")
      (node (ref "D16") (pin "3") (pinfunction "3_3") (pintype "passive"))
      (node (ref "R20") (pin "2") (pinfunction "2_2") (pintype "passive"))
      (node (ref "U4") (pin "29") (pinfunction "GPIO5_29") (pintype "passive"))
    )
    (net (code "37") (name "/OI5") (class "Default")
      (node (ref "D17") (pin "3") (pinfunction "3_3") (pintype "passive"))
      (node (ref "R21") (pin "2") (pinfunction "2_2") (pintype "passive"))
      (node (ref "U4") (pin "31") (pinfunction "GPIO6_31") (pintype "passive"))
    )
    (net (code "38") (name "/OI6") (class "Default")
      (node (ref "D18") (pin "3") (pinfunction "3_3") (pintype "passive"))
      (node (ref "R22") (pin "2") (pinfunction "2_2") (pintype "passive"))
      (node (ref "U4") (pin "36") (pinfunction "GPIO16_36") (pintype "passive"))
    )
    (net (code "39") (name "/OI7") (class "Default")
      (node (ref "D19") (pin "3") (pinfunction "3_3") (pintype "passive"))
      (node (ref "R23") (pin "2") (pinfunction "2_2") (pintype "passive"))
      (node (ref "U4") (pin "11") (pinfunction "GPIO17_11") (pintype "passive"))
    )
    (net (code "40") (name "/OI8") (class "Default")
      (node (ref "D20") (pin "3") (pinfunction "3_3") (pintype "passive"))
      (node (ref "R24") (pin "2") (pinfunction "2_2") (pintype "passive"))
      (node (ref "U4") (pin "38") (pinfunction "GPIO20_38") (pintype "passive"))
    )
    (net (code "41") (name "/RXD") (class "Default")
      (node (ref "J12") (pin "1") (pinfunction "1_1") (pintype "passive"))
      (node (ref "U4") (pin "10") (pinfunction "RXD_10") (pintype "passive"))
    )
    (net (code "42") (name "/Rele1") (class "Default")
      (node (ref "R13") (pin "1") (pinfunction "1_1") (pintype "passive"))
      (node (ref "U4") (pin "13") (pinfunction "GPIO27_13") (pintype "passive"))
    )
    (net (code "43") (name "/Rele2") (class "Default")
      (node (ref "R14") (pin "1") (pinfunction "1_1") (pintype "passive"))
      (node (ref "U4") (pin "15") (pinfunction "GPIO22_15") (pintype "passive"))
    )
    (net (code "44") (name "/Rele3") (class "Default")
      (node (ref "R15") (pin "1") (pinfunction "1_1") (pintype "passive"))
      (node (ref "U4") (pin "37") (pinfunction "GPIO26_37") (pintype "passive"))
    )
    (net (code "45") (name "/Rele4") (class "Default")
      (node (ref "R16") (pin "1") (pinfunction "1_1") (pintype "passive"))
      (node (ref "U4") (pin "16") (pinfunction "GPIO23_16") (pintype "passive"))
    )
    (net (code "46") (name "/SCL") (class "Default")
      (node (ref "J10") (pin "2") (pinfunction "2_2") (pintype "passive"))
      (node (ref "U4") (pin "5") (pinfunction "SCL_5") (pintype "passive"))
    )
    (net (code "47") (name "/SCLK") (class "Default")
      (node (ref "J11") (pin "3") (pinfunction "3_3") (pintype "passive"))
      (node (ref "U4") (pin "23") (pinfunction "SCLK_23") (pintype "passive"))
    )
    (net (code "48") (name "/SDA") (class "Default")
      (node (ref "J10") (pin "1") (pinfunction "1_1") (pintype "passive"))
      (node (ref "U4") (pin "3") (pinfunction "SDA_3") (pintype "passive"))
    )
    (net (code "49") (name "/TXD") (class "Default")
      (node (ref "J12") (pin "2") (pinfunction "2_2") (pintype "passive"))
      (node (ref "U4") (pin "8") (pinfunction "TXD_8") (pintype "passive"))
    )
    (net (code "50") (name "3V3") (class "Default")
      (node (ref "C3") (pin "1") (pinfunction "1_1") (pintype "passive"))
      (node (ref "D13") (pin "4") (pinfunction "4_4") (pintype "passive"))
      (node (ref "D14") (pin "4") (pinfunction "4_4") (pintype "passive"))
      (node (ref "D15") (pin "4") (pinfunction "4_4") (pintype "passive"))
      (node (ref "D16") (pin "4") (pinfunction "4_4") (pintype "passive"))
      (node (ref "D17") (pin "4") (pinfunction "4_4") (pintype "passive"))
      (node (ref "D18") (pin "4") (pinfunction "4_4") (pintype "passive"))
      (node (ref "D19") (pin "4") (pinfunction "4_4") (pintype "passive"))
      (node (ref "D20") (pin "4") (pinfunction "4_4") (pintype "passive"))
      (node (ref "U1") (pin "3") (pinfunction "OUT_3") (pintype "power_in"))
      (node (ref "U4") (pin "1") (pinfunction "3.3V_1") (pintype "passive"))
      (node (ref "U4") (pin "17") (pinfunction "3.3V_17") (pintype "passive"))
    )
    (net (code "51") (name "GND") (class "Default")
      (node (ref "C1") (pin "1") (pinfunction "C_1") (pintype "passive"))
      (node (ref "C2") (pin "2") (pinfunction "2_2") (pintype "passive"))
      (node (ref "C3") (pin "2") (pinfunction "2_2") (pintype "passive"))
      (node (ref "C4") (pin "1") (pinfunction "C_1") (pintype "passive"))
      (node (ref "C5") (pin "1") (pinfunction "C_1") (pintype "passive"))
      (node (ref "D13") (pin "2") (pinfunction "2_2") (pintype "passive"))
      (node (ref "D14") (pin "2") (pinfunction "2_2") (pintype "passive"))
      (node (ref "D15") (pin "2") (pinfunction "2_2") (pintype "passive"))
      (node (ref "D16") (pin "2") (pinfunction "2_2") (pintype "passive"))
      (node (ref "D17") (pin "2") (pinfunction "2_2") (pintype "passive"))
      (node (ref "D18") (pin "2") (pinfunction "2_2") (pintype "passive"))
      (node (ref "D19") (pin "2") (pinfunction "2_2") (pintype "passive"))
      (node (ref "D20") (pin "2") (pinfunction "2_2") (pintype "passive"))
      (node (ref "J6") (pin "1") (pinfunction "1_1") (pintype "passive"))
      (node (ref "J6") (pin "2") (pinfunction "2_2") (pintype "passive"))
      (node (ref "J6") (pin "3") (pinfunction "3_3") (pintype "passive"))
      (node (ref "J6") (pin "4") (pinfunction "4_4") (pintype "passive"))
      (node (ref "J8") (pin "1") (pinfunction "1_1") (pintype "passive"))
      (node (ref "J8") (pin "2") (pinfunction "2_2") (pintype "passive"))
      (node (ref "J8") (pin "3") (pinfunction "3_3") (pintype "passive"))
      (node (ref "Q1") (pin "2") (pinfunction "E_2") (pintype "passive"))
      (node (ref "Q2") (pin "2") (pinfunction "E_2") (pintype "passive"))
      (node (ref "Q3") (pin "2") (pinfunction "E_2") (pintype "passive"))
      (node (ref "Q4") (pin "2") (pinfunction "E_2") (pintype "passive"))
      (node (ref "Q5") (pin "2") (pinfunction "E_2") (pintype "passive"))
      (node (ref "Q6") (pin "2") (pinfunction "E_2") (pintype "passive"))
      (node (ref "Q7") (pin "2") (pinfunction "E_2") (pintype "passive"))
      (node (ref "Q8") (pin "2") (pinfunction "E_2") (pintype "passive"))
      (node (ref "R17") (pin "1") (pinfunction "1_1") (pintype "passive"))
      (node (ref "R18") (pin "1") (pinfunction "1_1") (pintype "passive"))
      (node (ref "R19") (pin "1") (pinfunction "1_1") (pintype "passive"))
      (node (ref "R20") (pin "1") (pinfunction "1_1") (pintype "passive"))
      (node (ref "R21") (pin "1") (pinfunction "1_1") (pintype "passive"))
      (node (ref "R22") (pin "1") (pinfunction "1_1") (pintype "passive"))
      (node (ref "R23") (pin "1") (pinfunction "1_1") (pintype "passive"))
      (node (ref "R24") (pin "1") (pinfunction "1_1") (pintype "passive"))
      (node (ref "U1") (pin "2") (pinfunction "GND_2") (pintype "power_in"))
      (node (ref "U1") (pin "4") (pinfunction "GND_4") (pintype "power_in"))
      (node (ref "U2") (pin "16") (pinfunction "-V_OUTPUT_16") (pintype "passive"))
      (node (ref "U2") (pin "2") (pinfunction "-V_INPUT_2") (pintype "passive"))
      (node (ref "U2") (pin "3") (pinfunction "-V_INPUT_3") (pintype "passive"))
      (node (ref "U2") (pin "9") (pinfunction "-V_OUTPUT_9") (pintype "passive"))
      (node (ref "U3") (pin "1") (pinfunction "GND_1") (pintype "power_in"))
      (node (ref "U4") (pin "14") (pinfunction "GND_14") (pintype "passive"))
      (node (ref "U4") (pin "20") (pinfunction "GND_20") (pintype "passive"))
      (node (ref "U4") (pin "25") (pinfunction "GND_25") (pintype "passive"))
      (node (ref "U4") (pin "30") (pinfunction "GND_30") (pintype "passive"))
      (node (ref "U4") (pin "34") (pinfunction "GND_34") (pintype "passive"))
      (node (ref "U4") (pin "39") (pinfunction "GND_39") (pintype "passive"))
      (node (ref "U4") (pin "6") (pinfunction "GND_6") (pintype "passive"))
      (node (ref "U4") (pin "9") (pinfunction "GND_9") (pintype "passive"))
    )
    (net (code "52") (name "Net-(D1-Pad2)") (class "Default")
      (node (ref "D1") (pin "2") (pinfunction "2_2") (pintype "passive"))
      (node (ref "R1") (pin "1") (pinfunction "1_1") (pintype "passive"))
    )
    (net (code "53") (name "Net-(D1-Pad3)") (class "Default")
      (node (ref "D1") (pin "3") (pinfunction "3_3") (pintype "passive"))
      (node (ref "R9") (pin "1") (pinfunction "1_1") (pintype "passive"))
    )
    (net (code "54") (name "Net-(D2-Pad2)") (class "Default")
      (node (ref "D2") (pin "2") (pinfunction "2_2") (pintype "passive"))
      (node (ref "R2") (pin "1") (pinfunction "1_1") (pintype "passive"))
    )
    (net (code "55") (name "Net-(D2-Pad3)") (class "Default")
      (node (ref "D2") (pin "3") (pinfunction "3_3") (pintype "passive"))
      (node (ref "R10") (pin "1") (pinfunction "1_1") (pintype "passive"))
    )
    (net (code "56") (name "Net-(D3-Pad2)") (class "Default")
      (node (ref "D3") (pin "2") (pinfunction "2_2") (pintype "passive"))
      (node (ref "R3") (pin "1") (pinfunction "1_1") (pintype "passive"))
    )
    (net (code "57") (name "Net-(D3-Pad3)") (class "Default")
      (node (ref "D3") (pin "3") (pinfunction "3_3") (pintype "passive"))
      (node (ref "R11") (pin "1") (pinfunction "1_1") (pintype "passive"))
    )
    (net (code "58") (name "Net-(D4-Pad2)") (class "Default")
      (node (ref "D4") (pin "2") (pinfunction "2_2") (pintype "passive"))
      (node (ref "R4") (pin "1") (pinfunction "1_1") (pintype "passive"))
    )
    (net (code "59") (name "Net-(D4-Pad3)") (class "Default")
      (node (ref "D4") (pin "3") (pinfunction "3_3") (pintype "passive"))
      (node (ref "R12") (pin "1") (pinfunction "1_1") (pintype "passive"))
    )
    (net (code "60") (name "Net-(D5-Pad2)") (class "Default")
      (node (ref "D5") (pin "2") (pinfunction "2_2") (pintype "passive"))
      (node (ref "R5") (pin "2") (pinfunction "2_2") (pintype "passive"))
    )
    (net (code "61") (name "Net-(D6-Pad2)") (class "Default")
      (node (ref "D6") (pin "2") (pinfunction "2_2") (pintype "passive"))
      (node (ref "R6") (pin "2") (pinfunction "2_2") (pintype "passive"))
    )
    (net (code "62") (name "Net-(D7-Pad2)") (class "Default")
      (node (ref "D7") (pin "2") (pinfunction "2_2") (pintype "passive"))
      (node (ref "R7") (pin "2") (pinfunction "2_2") (pintype "passive"))
    )
    (net (code "63") (name "Net-(D8-Pad2)") (class "Default")
      (node (ref "D8") (pin "2") (pinfunction "2_2") (pintype "passive"))
      (node (ref "R8") (pin "2") (pinfunction "2_2") (pintype "passive"))
    )
    (net (code "64") (name "Net-(Q1-B)") (class "Default")
      (node (ref "Q1") (pin "1") (pinfunction "B_1") (pintype "passive"))
      (node (ref "R13") (pin "2") (pinfunction "2_2") (pintype "passive"))
    )
    (net (code "65") (name "Net-(Q1-C)") (class "Default")
      (node (ref "Q1") (pin "3") (pinfunction "C_3") (pintype "passive"))
      (node (ref "R1") (pin "2") (pinfunction "2_2") (pintype "passive"))
    )
    (net (code "66") (name "Net-(Q2-B)") (class "Default")
      (node (ref "Q2") (pin "1") (pinfunction "B_1") (pintype "passive"))
      (node (ref "R14") (pin "2") (pinfunction "2_2") (pintype "passive"))
    )
    (net (code "67") (name "Net-(Q2-C)") (class "Default")
      (node (ref "Q2") (pin "3") (pinfunction "C_3") (pintype "passive"))
      (node (ref "R2") (pin "2") (pinfunction "2_2") (pintype "passive"))
    )
    (net (code "68") (name "Net-(Q3-B)") (class "Default")
      (node (ref "Q3") (pin "1") (pinfunction "B_1") (pintype "passive"))
      (node (ref "R15") (pin "2") (pinfunction "2_2") (pintype "passive"))
    )
    (net (code "69") (name "Net-(Q3-C)") (class "Default")
      (node (ref "Q3") (pin "3") (pinfunction "C_3") (pintype "passive"))
      (node (ref "R3") (pin "2") (pinfunction "2_2") (pintype "passive"))
    )
    (net (code "70") (name "Net-(Q4-B)") (class "Default")
      (node (ref "Q4") (pin "1") (pinfunction "B_1") (pintype "passive"))
      (node (ref "R16") (pin "2") (pinfunction "2_2") (pintype "passive"))
    )
    (net (code "71") (name "Net-(Q4-C)") (class "Default")
      (node (ref "Q4") (pin "3") (pinfunction "C_3") (pintype "passive"))
      (node (ref "R4") (pin "2") (pinfunction "2_2") (pintype "passive"))
    )
    (net (code "72") (name "Net-(Q5-B)") (class "Default")
      (node (ref "Q5") (pin "1") (pinfunction "B_1") (pintype "passive"))
      (node (ref "R9") (pin "2") (pinfunction "2_2") (pintype "passive"))
    )
    (net (code "73") (name "Net-(Q5-C)") (class "Default")
      (node (ref "D9") (pin "1") (pinfunction "1_1") (pintype "passive"))
      (node (ref "K1") (pin "A2") (pinfunction "A2_A2") (pintype "passive"))
      (node (ref "Q5") (pin "3") (pinfunction "C_3") (pintype "passive"))
      (node (ref "R5") (pin "1") (pinfunction "1_1") (pintype "passive"))
    )
    (net (code "74") (name "Net-(Q6-B)") (class "Default")
      (node (ref "Q6") (pin "1") (pinfunction "B_1") (pintype "passive"))
      (node (ref "R10") (pin "2") (pinfunction "2_2") (pintype "passive"))
    )
    (net (code "75") (name "Net-(Q6-C)") (class "Default")
      (node (ref "D10") (pin "1") (pinfunction "1_1") (pintype "passive"))
      (node (ref "K2") (pin "A2") (pinfunction "A2_A2") (pintype "passive"))
      (node (ref "Q6") (pin "3") (pinfunction "C_3") (pintype "passive"))
      (node (ref "R6") (pin "1") (pinfunction "1_1") (pintype "passive"))
    )
    (net (code "76") (name "Net-(Q7-B)") (class "Default")
      (node (ref "Q7") (pin "1") (pinfunction "B_1") (pintype "passive"))
      (node (ref "R11") (pin "2") (pinfunction "2_2") (pintype "passive"))
    )
    (net (code "77") (name "Net-(Q7-C)") (class "Default")
      (node (ref "D11") (pin "1") (pinfunction "1_1") (pintype "passive"))
      (node (ref "K3") (pin "A2") (pinfunction "A2_A2") (pintype "passive"))
      (node (ref "Q7") (pin "3") (pinfunction "C_3") (pintype "passive"))
      (node (ref "R7") (pin "1") (pinfunction "1_1") (pintype "passive"))
    )
    (net (code "78") (name "Net-(Q8-B)") (class "Default")
      (node (ref "Q8") (pin "1") (pinfunction "B_1") (pintype "passive"))
      (node (ref "R12") (pin "2") (pinfunction "2_2") (pintype "passive"))
    )
    (net (code "79") (name "Net-(Q8-C)") (class "Default")
      (node (ref "D12") (pin "1") (pinfunction "1_1") (pintype "passive"))
      (node (ref "K4") (pin "A2") (pinfunction "A2_A2") (pintype "passive"))
      (node (ref "Q8") (pin "3") (pinfunction "C_3") (pintype "passive"))
      (node (ref "R8") (pin "1") (pinfunction "1_1") (pintype "passive"))
    )
    (net (code "80") (name "unconnected-(U2-NO_CONECT-Pad10)") (class "Default")
      (node (ref "U2") (pin "10") (pinfunction "NO_CONECT_10") (pintype "passive"))
    )
    (net (code "81") (name "unconnected-(U2-NO_CONECT-Pad15)") (class "Default")
      (node (ref "U2") (pin "15") (pinfunction "NO_CONECT_15") (pintype "passive"))
    )
    (net (code "82") (name "unconnected-(U2-NO_PIN-Pad1)") (class "Default")
      (node (ref "U2") (pin "1") (pinfunction "NO_PIN_1") (pintype "passive"))
    )
    (net (code "83") (name "unconnected-(U2-NO_PIN-Pad12)") (class "Default")
      (node (ref "U2") (pin "12") (pinfunction "NO_PIN_12") (pintype "passive"))
    )
    (net (code "84") (name "unconnected-(U2-NO_PIN-Pad13)") (class "Default")
      (node (ref "U2") (pin "13") (pinfunction "NO_PIN_13") (pintype "passive"))
    )
    (net (code "85") (name "unconnected-(U2-NO_PIN-Pad24)") (class "Default")
      (node (ref "U2") (pin "24") (pinfunction "NO_PIN_24") (pintype "passive"))
    )
    (net (code "86") (name "unconnected-(U3-TAB-Pad4)") (class "Default")
      (node (ref "U3") (pin "4") (pinfunction "TAB_4") (pintype "power_in"))
    )
    (net (code "87") (name "unconnected-(U4-DNC-Pad27)") (class "Default")
      (node (ref "U4") (pin "27") (pinfunction "DNC_27") (pintype "passive"))
    )
    (net (code "88") (name "unconnected-(U4-DNC-Pad28)") (class "Default")
      (node (ref "U4") (pin "28") (pinfunction "DNC_28") (pintype "passive"))
    )
  )
)
